# midi-in-board.net
KiCad netlist of a schematic drawn in EAGLE
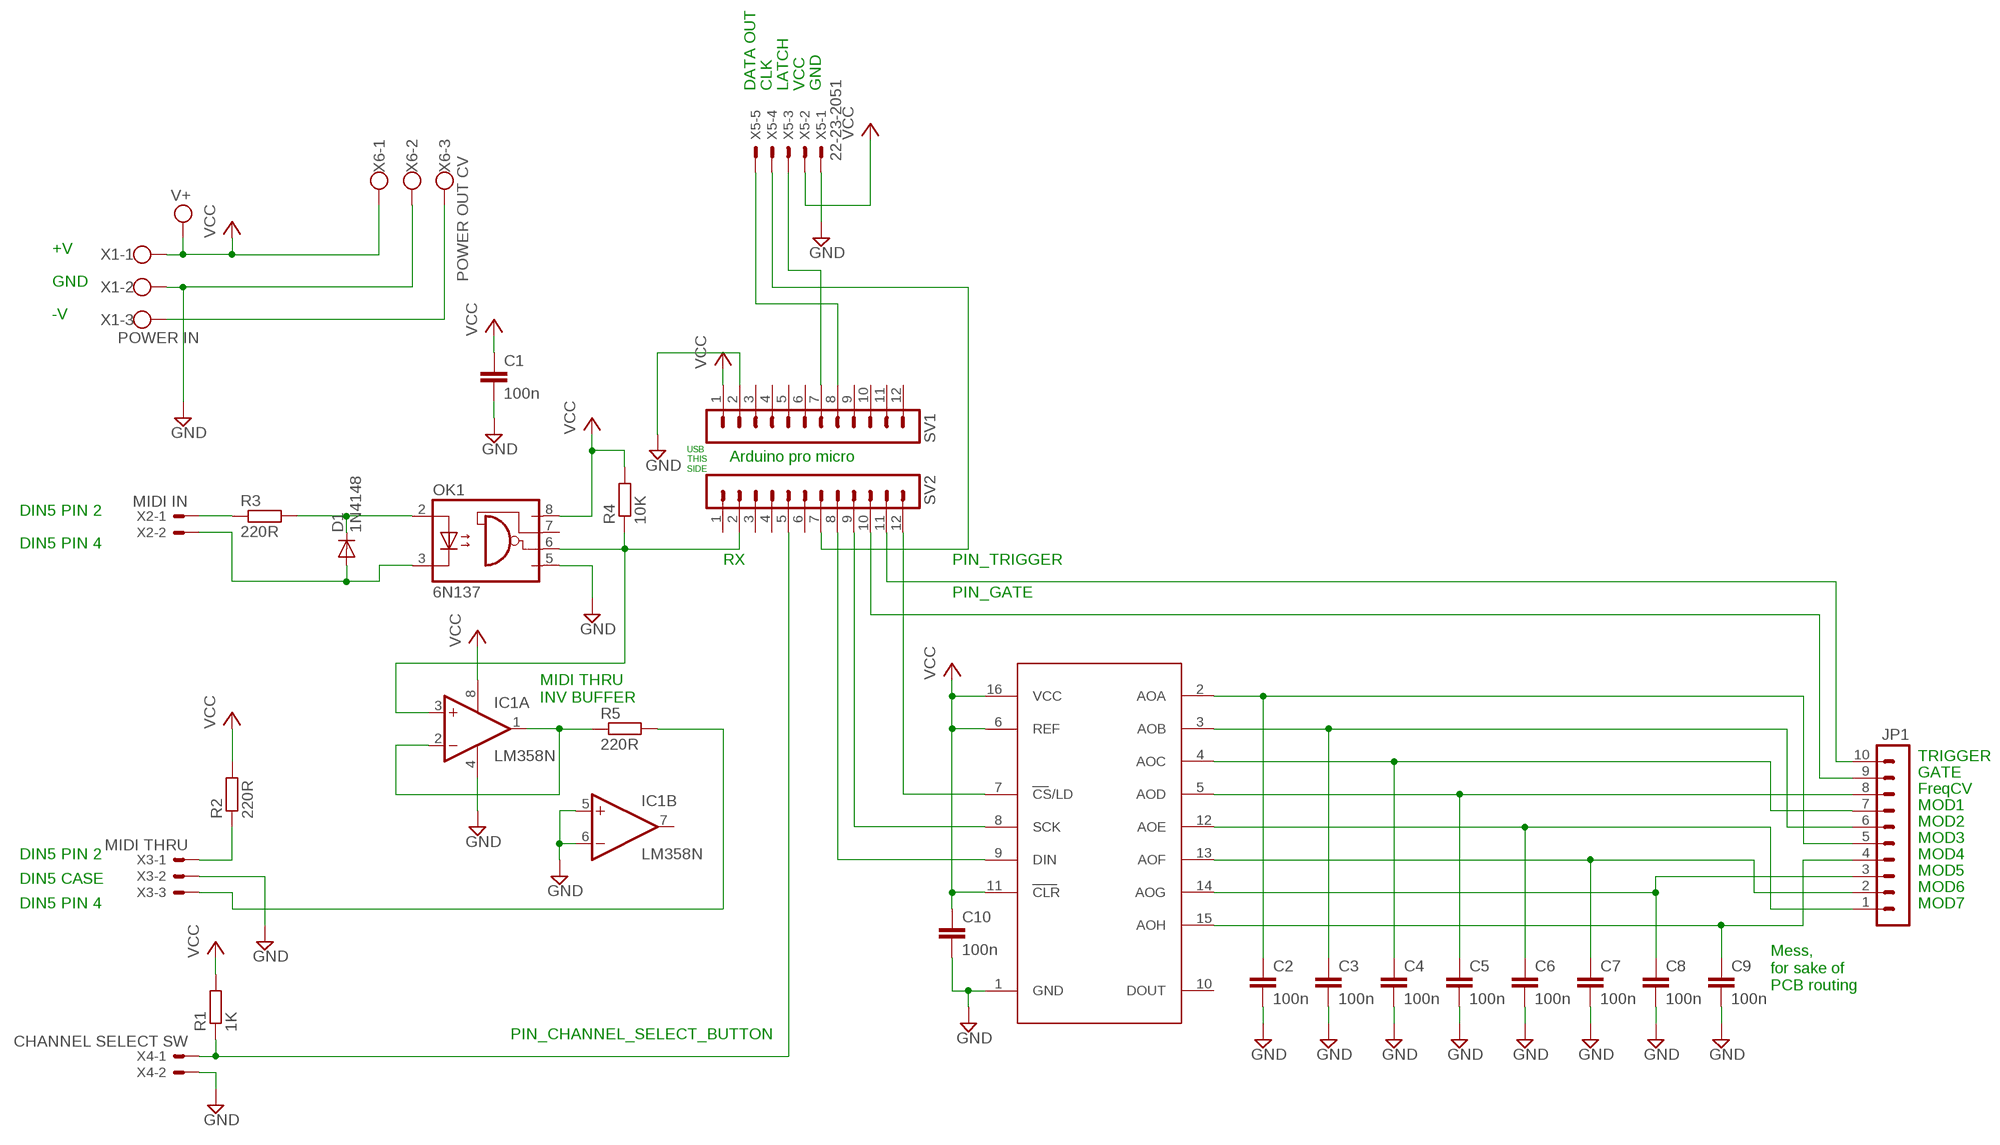
[diagram p0: schematic, sheet 1]

(export (version "E")
  (design (tool "Eeschema 10.0.6"))
  (components
    (comp (ref "C1")
      (value "100n")
      (footprint "eagle-import:C050-024X044")
      (libsource (lib "eagle-import") (part "C-EU050-024X044"))
    )
    (comp (ref "C2")
      (value "100n")
      (footprint "eagle-import:C050-024X044")
      (libsource (lib "eagle-import") (part "C-EU050-024X044"))
    )
    (comp (ref "C3")
      (value "100n")
      (footprint "eagle-import:C050-024X044")
      (libsource (lib "eagle-import") (part "C-EU050-024X044"))
    )
    (comp (ref "C4")
      (value "100n")
      (footprint "eagle-import:C050-024X044")
      (libsource (lib "eagle-import") (part "C-EU050-024X044"))
    )
    (comp (ref "C5")
      (value "100n")
      (footprint "eagle-import:C050-024X044")
      (libsource (lib "eagle-import") (part "C-EU050-024X044"))
    )
    (comp (ref "C6")
      (value "100n")
      (footprint "eagle-import:C050-024X044")
      (libsource (lib "eagle-import") (part "C-EU050-024X044"))
    )
    (comp (ref "C7")
      (value "100n")
      (footprint "eagle-import:C050-024X044")
      (libsource (lib "eagle-import") (part "C-EU050-024X044"))
    )
    (comp (ref "C8")
      (value "100n")
      (footprint "eagle-import:C050-024X044")
      (libsource (lib "eagle-import") (part "C-EU050-024X044"))
    )
    (comp (ref "C9")
      (value "100n")
      (footprint "eagle-import:C050-024X044")
      (libsource (lib "eagle-import") (part "C-EU050-024X044"))
    )
    (comp (ref "C10")
      (value "100n")
      (footprint "eagle-import:C050-024X044")
      (libsource (lib "eagle-import") (part "C-EU050-024X044"))
    )
    (comp (ref "D1")
      (value "1N4148")
      (footprint "eagle-import:DO35-7")
      (libsource (lib "eagle-import") (part "1N4148DO35-7"))
    )
    (comp (ref "IC1")
      (value "LM358N")
      (footprint "eagle-import:DIL08")
      (libsource (lib "eagle-import") (part "LM358N"))
    )
    (comp (ref "JP1")
      (value "MA10-1")
      (footprint "eagle-import:MA10-1")
      (libsource (lib "eagle-import") (part "MA10-1"))
    )
    (comp (ref "OK1")
      (value "6N137")
      (footprint "eagle-import:DIL08")
      (libsource (lib "eagle-import") (part "6N137"))
    )
    (comp (ref "R1")
      (value "1K")
      (footprint "eagle-import:0207_7")
      (libsource (lib "eagle-import") (part "R-EU_0207/7"))
    )
    (comp (ref "R2")
      (value "220R")
      (footprint "eagle-import:0207_7")
      (libsource (lib "eagle-import") (part "R-EU_0207/7"))
    )
    (comp (ref "R3")
      (value "220R")
      (footprint "eagle-import:0207_7")
      (libsource (lib "eagle-import") (part "R-EU_0207/7"))
    )
    (comp (ref "R4")
      (value "10K")
      (footprint "eagle-import:0207_7")
      (libsource (lib "eagle-import") (part "R-EU_0207/7"))
    )
    (comp (ref "R5")
      (value "220R")
      (footprint "eagle-import:0207_7")
      (libsource (lib "eagle-import") (part "R-EU_0207/7"))
    )
    (comp (ref "SV1")
      (value "MA12-1")
      (footprint "eagle-import:MA12-1")
      (libsource (lib "eagle-import") (part "MA12-1"))
    )
    (comp (ref "SV2")
      (value "MA12-1")
      (footprint "eagle-import:MA12-1")
      (libsource (lib "eagle-import") (part "MA12-1"))
    )
    (comp (ref "U$1")
      (value "LTC1660")
      (footprint "eagle-import:DIL16")
      (libsource (lib "eagle-import") (part "LTC1660"))
    )
    (comp (ref "X1")
      (value "POWER IN")
      (footprint "eagle-import:W237-103")
      (fields (field (name "MPN") "237-103"))
      (libsource (lib "eagle-import") (part "W237-103"))
    )
    (comp (ref "X2")
      (value "MIDI IN")
      (footprint "eagle-import:22-23-2021")
      (fields (field (name "MF") "MOLEX") (field (name "MPN") "22-23-2021"))
      (libsource (lib "eagle-import") (part "22-23-2021"))
    )
    (comp (ref "X3")
      (value "MIDI THRU")
      (footprint "eagle-import:22-23-2031")
      (fields (field (name "MF") "MOLEX") (field (name "MPN") "22-23-2031"))
      (libsource (lib "eagle-import") (part "22-23-2031"))
    )
    (comp (ref "X4")
      (value "CHANNEL SELECT SW")
      (footprint "eagle-import:22-23-2021")
      (fields (field (name "MF") "MOLEX") (field (name "MPN") "22-23-2021"))
      (libsource (lib "eagle-import") (part "22-23-2021"))
    )
    (comp (ref "X5")
      (value "22-23-2051")
      (footprint "eagle-import:22-23-2051")
      (fields (field (name "MF") "MOLEX"))
      (libsource (lib "eagle-import") (part "22-23-2051"))
    )
    (comp (ref "X6")
      (value "POWER OUT CV")
      (footprint "eagle-import:W237-103")
      (fields (field (name "MPN") "237-103"))
      (libsource (lib "eagle-import") (part "W237-103"))
    )
  )
  (nets
    (net (code "1") (name "GND") (class "Default")
      (node (ref "C1") (pin "2") (pinfunction "2_2") (pintype "passive"))
      (node (ref "C10") (pin "2") (pinfunction "2_2") (pintype "passive"))
      (node (ref "C2") (pin "2") (pinfunction "2_2") (pintype "passive"))
      (node (ref "C3") (pin "2") (pinfunction "2_2") (pintype "passive"))
      (node (ref "C4") (pin "2") (pinfunction "2_2") (pintype "passive"))
      (node (ref "C5") (pin "2") (pinfunction "2_2") (pintype "passive"))
      (node (ref "C6") (pin "2") (pinfunction "2_2") (pintype "passive"))
      (node (ref "C7") (pin "2") (pinfunction "2_2") (pintype "passive"))
      (node (ref "C8") (pin "2") (pinfunction "2_2") (pintype "passive"))
      (node (ref "C9") (pin "2") (pinfunction "2_2") (pintype "passive"))
      (node (ref "IC1") (pin "4") (pinfunction "V-_4") (pintype "power_in"))
      (node (ref "IC1") (pin "5") (pinfunction "+IN_5") (pintype "input"))
      (node (ref "IC1") (pin "6") (pinfunction "-IN_6") (pintype "input"))
      (node (ref "OK1") (pin "5") (pinfunction "GND_5") (pintype "passive"))
      (node (ref "SV1") (pin "2") (pinfunction "2_2") (pintype "passive"))
      (node (ref "U$1") (pin "1") (pinfunction "GND_1") (pintype "bidirectional"))
      (node (ref "X1") (pin "2") (pinfunction "KL_2") (pintype "passive"))
      (node (ref "X3") (pin "2") (pinfunction "S_2") (pintype "passive"))
      (node (ref "X4") (pin "2") (pinfunction "S_2") (pintype "passive"))
      (node (ref "X5") (pin "1") (pinfunction "S_1") (pintype "passive"))
      (node (ref "X6") (pin "2") (pinfunction "KL_2") (pintype "passive"))
    )
    (net (code "2") (name "Net-(IC1A-+IN)") (class "Default")
      (node (ref "IC1") (pin "3") (pinfunction "+IN_3") (pintype "input"))
      (node (ref "OK1") (pin "6") (pinfunction "VO_6") (pintype "passive"))
      (node (ref "R4") (pin "1") (pinfunction "1_1") (pintype "passive"))
      (node (ref "SV2") (pin "2") (pinfunction "2_2") (pintype "passive"))
    )
    (net (code "3") (name "Net-(IC1A--IN)") (class "Default")
      (node (ref "IC1") (pin "1") (pinfunction "OUT_1") (pintype "output"))
      (node (ref "IC1") (pin "2") (pinfunction "-IN_2") (pintype "input"))
      (node (ref "R5") (pin "1") (pinfunction "1_1") (pintype "passive"))
    )
    (net (code "4") (name "Net-(JP1-Pad9)") (class "Default")
      (node (ref "JP1") (pin "9") (pinfunction "9_9") (pintype "passive"))
      (node (ref "SV2") (pin "10") (pinfunction "10_10") (pintype "passive"))
    )
    (net (code "5") (name "Net-(JP1-Pad10)") (class "Default")
      (node (ref "JP1") (pin "10") (pinfunction "10_10") (pintype "passive"))
      (node (ref "SV2") (pin "11") (pinfunction "11_11") (pintype "passive"))
    )
    (net (code "6") (name "Net-(OK1-A)") (class "Default")
      (node (ref "D1") (pin "C") (pinfunction "C_C") (pintype "passive"))
      (node (ref "OK1") (pin "2") (pinfunction "A_2") (pintype "passive"))
      (node (ref "R3") (pin "2") (pinfunction "2_2") (pintype "passive"))
    )
    (net (code "7") (name "Net-(OK1-C)") (class "Default")
      (node (ref "D1") (pin "A") (pinfunction "A_A") (pintype "passive"))
      (node (ref "OK1") (pin "3") (pinfunction "C_3") (pintype "passive"))
      (node (ref "X2") (pin "2") (pinfunction "S_2") (pintype "passive"))
    )
    (net (code "8") (name "Net-(U$1-AOA)") (class "Default")
      (node (ref "C2") (pin "1") (pinfunction "1_1") (pintype "passive"))
      (node (ref "JP1") (pin "5") (pinfunction "5_5") (pintype "passive"))
      (node (ref "U$1") (pin "2") (pinfunction "AOA_2") (pintype "bidirectional"))
    )
    (net (code "9") (name "Net-(U$1-AOB)") (class "Default")
      (node (ref "C3") (pin "1") (pinfunction "1_1") (pintype "passive"))
      (node (ref "JP1") (pin "6") (pinfunction "6_6") (pintype "passive"))
      (node (ref "U$1") (pin "3") (pinfunction "AOB_3") (pintype "bidirectional"))
    )
    (net (code "10") (name "Net-(U$1-AOC)") (class "Default")
      (node (ref "C4") (pin "1") (pinfunction "1_1") (pintype "passive"))
      (node (ref "JP1") (pin "7") (pinfunction "7_7") (pintype "passive"))
      (node (ref "U$1") (pin "4") (pinfunction "AOC_4") (pintype "bidirectional"))
    )
    (net (code "11") (name "Net-(U$1-AOD)") (class "Default")
      (node (ref "C5") (pin "1") (pinfunction "1_1") (pintype "passive"))
      (node (ref "JP1") (pin "8") (pinfunction "8_8") (pintype "passive"))
      (node (ref "U$1") (pin "5") (pinfunction "AOD_5") (pintype "bidirectional"))
    )
    (net (code "12") (name "Net-(U$1-AOE)") (class "Default")
      (node (ref "C6") (pin "1") (pinfunction "1_1") (pintype "passive"))
      (node (ref "JP1") (pin "1") (pinfunction "1_1") (pintype "passive"))
      (node (ref "U$1") (pin "12") (pinfunction "AOE_12") (pintype "bidirectional"))
    )
    (net (code "13") (name "Net-(U$1-AOF)") (class "Default")
      (node (ref "C7") (pin "1") (pinfunction "1_1") (pintype "passive"))
      (node (ref "JP1") (pin "2") (pinfunction "2_2") (pintype "passive"))
      (node (ref "U$1") (pin "13") (pinfunction "AOF_13") (pintype "bidirectional"))
    )
    (net (code "14") (name "Net-(U$1-AOG)") (class "Default")
      (node (ref "C8") (pin "1") (pinfunction "1_1") (pintype "passive"))
      (node (ref "JP1") (pin "3") (pinfunction "3_3") (pintype "passive"))
      (node (ref "U$1") (pin "14") (pinfunction "AOG_14") (pintype "bidirectional"))
    )
    (net (code "15") (name "Net-(U$1-AOH)") (class "Default")
      (node (ref "C9") (pin "1") (pinfunction "1_1") (pintype "passive"))
      (node (ref "JP1") (pin "4") (pinfunction "4_4") (pintype "passive"))
      (node (ref "U$1") (pin "15") (pinfunction "AOH_15") (pintype "bidirectional"))
    )
    (net (code "16") (name "Net-(U$1-CS{slash}LD)") (class "Default")
      (node (ref "SV2") (pin "12") (pinfunction "12_12") (pintype "passive"))
      (node (ref "U$1") (pin "7") (pinfunction "CS/LD_7") (pintype "bidirectional"))
    )
    (net (code "17") (name "Net-(U$1-DIN)") (class "Default")
      (node (ref "SV2") (pin "8") (pinfunction "8_8") (pintype "passive"))
      (node (ref "U$1") (pin "9") (pinfunction "DIN_9") (pintype "bidirectional"))
    )
    (net (code "18") (name "Net-(U$1-SCK)") (class "Default")
      (node (ref "SV2") (pin "9") (pinfunction "9_9") (pintype "passive"))
      (node (ref "U$1") (pin "8") (pinfunction "SCK_8") (pintype "bidirectional"))
    )
    (net (code "19") (name "Net-(X1C-KL)") (class "Default")
      (node (ref "X1") (pin "3") (pinfunction "KL_3") (pintype "passive"))
      (node (ref "X6") (pin "3") (pinfunction "KL_3") (pintype "passive"))
    )
    (net (code "20") (name "Net-(X2A-S)") (class "Default")
      (node (ref "R3") (pin "1") (pinfunction "1_1") (pintype "passive"))
      (node (ref "X2") (pin "1") (pinfunction "S_1") (pintype "passive"))
    )
    (net (code "21") (name "Net-(X3A-S)") (class "Default")
      (node (ref "R2") (pin "1") (pinfunction "1_1") (pintype "passive"))
      (node (ref "X3") (pin "1") (pinfunction "S_1") (pintype "passive"))
    )
    (net (code "22") (name "Net-(X3C-S)") (class "Default")
      (node (ref "R5") (pin "2") (pinfunction "2_2") (pintype "passive"))
      (node (ref "X3") (pin "3") (pinfunction "S_3") (pintype "passive"))
    )
    (net (code "23") (name "Net-(X4A-S)") (class "Default")
      (node (ref "R1") (pin "1") (pinfunction "1_1") (pintype "passive"))
      (node (ref "SV2") (pin "5") (pinfunction "5_5") (pintype "passive"))
      (node (ref "X4") (pin "1") (pinfunction "S_1") (pintype "passive"))
    )
    (net (code "24") (name "Net-(X5C-S)") (class "Default")
      (node (ref "SV1") (pin "7") (pinfunction "7_7") (pintype "passive"))
      (node (ref "X5") (pin "3") (pinfunction "S_3") (pintype "passive"))
    )
    (net (code "25") (name "Net-(X5D-S)") (class "Default")
      (node (ref "SV2") (pin "7") (pinfunction "7_7") (pintype "passive"))
      (node (ref "X5") (pin "4") (pinfunction "S_4") (pintype "passive"))
    )
    (net (code "26") (name "Net-(X5E-S)") (class "Default")
      (node (ref "SV1") (pin "8") (pinfunction "8_8") (pintype "passive"))
      (node (ref "X5") (pin "5") (pinfunction "S_5") (pintype "passive"))
    )
    (net (code "27") (name "V+") (class "Default")
      (node (ref "C1") (pin "1") (pinfunction "1_1") (pintype "passive"))
      (node (ref "C10") (pin "1") (pinfunction "1_1") (pintype "passive"))
      (node (ref "IC1") (pin "8") (pinfunction "V+_8") (pintype "power_in"))
      (node (ref "OK1") (pin "8") (pinfunction "VCC_8") (pintype "passive"))
      (node (ref "R1") (pin "2") (pinfunction "2_2") (pintype "passive"))
      (node (ref "R2") (pin "2") (pinfunction "2_2") (pintype "passive"))
      (node (ref "R4") (pin "2") (pinfunction "2_2") (pintype "passive"))
      (node (ref "SV1") (pin "1") (pinfunction "1_1") (pintype "passive"))
      (node (ref "U$1") (pin "11") (pinfunction "CLR_11") (pintype "bidirectional"))
      (node (ref "U$1") (pin "16") (pinfunction "VCC_16") (pintype "bidirectional"))
      (node (ref "U$1") (pin "6") (pinfunction "REF_6") (pintype "bidirectional"))
      (node (ref "X1") (pin "1") (pinfunction "KL_1") (pintype "passive"))
      (node (ref "X5") (pin "2") (pinfunction "S_2") (pintype "passive"))
      (node (ref "X6") (pin "1") (pinfunction "KL_1") (pintype "passive"))
    )
    (net (code "28") (name "unconnected-(IC1B-OUT-Pad7)") (class "Default")
      (node (ref "IC1") (pin "7") (pinfunction "OUT_7") (pintype "output"))
    )
    (net (code "29") (name "unconnected-(OK1-VE-Pad7)") (class "Default")
      (node (ref "OK1") (pin "7") (pinfunction "VE_7") (pintype "passive"))
    )
    (net (code "30") (name "unconnected-(SV1-Pad3)") (class "Default")
      (node (ref "SV1") (pin "3") (pinfunction "3_3") (pintype "passive"))
    )
    (net (code "31") (name "unconnected-(SV1-Pad4)") (class "Default")
      (node (ref "SV1") (pin "4") (pinfunction "4_4") (pintype "passive"))
    )
    (net (code "32") (name "unconnected-(SV1-Pad5)") (class "Default")
      (node (ref "SV1") (pin "5") (pinfunction "5_5") (pintype "passive"))
    )
    (net (code "33") (name "unconnected-(SV1-Pad6)") (class "Default")
      (node (ref "SV1") (pin "6") (pinfunction "6_6") (pintype "passive"))
    )
    (net (code "34") (name "unconnected-(SV1-Pad9)") (class "Default")
      (node (ref "SV1") (pin "9") (pinfunction "9_9") (pintype "passive"))
    )
    (net (code "35") (name "unconnected-(SV1-Pad10)") (class "Default")
      (node (ref "SV1") (pin "10") (pinfunction "10_10") (pintype "passive"))
    )
    (net (code "36") (name "unconnected-(SV1-Pad11)") (class "Default")
      (node (ref "SV1") (pin "11") (pinfunction "11_11") (pintype "passive"))
    )
    (net (code "37") (name "unconnected-(SV1-Pad12)") (class "Default")
      (node (ref "SV1") (pin "12") (pinfunction "12_12") (pintype "passive"))
    )
    (net (code "38") (name "unconnected-(SV2-Pad1)") (class "Default")
      (node (ref "SV2") (pin "1") (pinfunction "1_1") (pintype "passive"))
    )
    (net (code "39") (name "unconnected-(SV2-Pad3)") (class "Default")
      (node (ref "SV2") (pin "3") (pinfunction "3_3") (pintype "passive"))
    )
    (net (code "40") (name "unconnected-(SV2-Pad4)") (class "Default")
      (node (ref "SV2") (pin "4") (pinfunction "4_4") (pintype "passive"))
    )
    (net (code "41") (name "unconnected-(SV2-Pad6)") (class "Default")
      (node (ref "SV2") (pin "6") (pinfunction "6_6") (pintype "passive"))
    )
    (net (code "42") (name "unconnected-(U$1-DOUT-Pad10)") (class "Default")
      (node (ref "U$1") (pin "10") (pinfunction "DOUT_10") (pintype "bidirectional"))
    )
  )
)
